# connectors.net
KiCad netlist of a schematic drawn in EAGLE
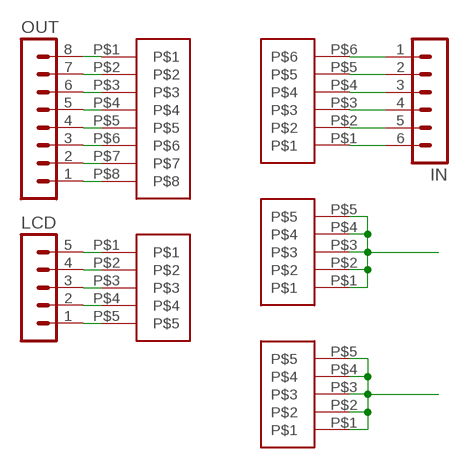
[diagram p0: schematic, sheet 1]

(export (version "E")
  (design (tool "Eeschema 10.0.6"))
  (components
    (comp (ref "IN")
      (value "MA06-1")
      (footprint "eagle-import:MA06-1")
      (libsource (lib "eagle-import") (part "MA06-1"))
    )
    (comp (ref "LCD")
      (value "MA05-1")
      (footprint "eagle-import:MA05-1")
      (libsource (lib "eagle-import") (part "MA05-1"))
    )
    (comp (ref "OUT")
      (value "MA08-1")
      (footprint "eagle-import:MA08-1")
      (libsource (lib "eagle-import") (part "MA08-1"))
    )
    (comp (ref "U$1")
      (value "KOSTKA_2.5MM_X8")
      (footprint "eagle-import:X8")
      (libsource (lib "eagle-import") (part "KOSTKA_2.5MM_X8"))
    )
    (comp (ref "U$2")
      (value "KOSTKA_2.5MM_X5")
      (footprint "eagle-import:X5")
      (libsource (lib "eagle-import") (part "KOSTKA_2.5MM_X5"))
    )
    (comp (ref "U$3")
      (value "KOSTKA_2.5MM_X6")
      (footprint "eagle-import:X6")
      (libsource (lib "eagle-import") (part "KOSTKA_2.5MM_X6"))
    )
    (comp (ref "U$4")
      (value "KOSTKA_2.5MM_X5")
      (footprint "eagle-import:X5")
      (libsource (lib "eagle-import") (part "KOSTKA_2.5MM_X5"))
    )
    (comp (ref "U$6")
      (value "KOSTKA_2.5MM_X5")
      (footprint "eagle-import:X5")
      (libsource (lib "eagle-import") (part "KOSTKA_2.5MM_X5"))
    )
  )
  (nets
    (net (code "1") (name "Net-(IN-Pad1)") (class "Default")
      (node (ref "IN") (pin "1") (pinfunction "1_1") (pintype "passive"))
      (node (ref "U$3") (pin "P$6") (pinfunction "P$6_P$6") (pintype "bidirectional"))
    )
    (net (code "2") (name "Net-(IN-Pad2)") (class "Default")
      (node (ref "IN") (pin "2") (pinfunction "2_2") (pintype "passive"))
      (node (ref "U$3") (pin "P$5") (pinfunction "P$5_P$5") (pintype "bidirectional"))
    )
    (net (code "3") (name "Net-(IN-Pad3)") (class "Default")
      (node (ref "IN") (pin "3") (pinfunction "3_3") (pintype "passive"))
      (node (ref "U$3") (pin "P$4") (pinfunction "P$4_P$4") (pintype "bidirectional"))
    )
    (net (code "4") (name "Net-(IN-Pad4)") (class "Default")
      (node (ref "IN") (pin "4") (pinfunction "4_4") (pintype "passive"))
      (node (ref "U$3") (pin "P$3") (pinfunction "P$3_P$3") (pintype "bidirectional"))
    )
    (net (code "5") (name "Net-(IN-Pad5)") (class "Default")
      (node (ref "IN") (pin "5") (pinfunction "5_5") (pintype "passive"))
      (node (ref "U$3") (pin "P$2") (pinfunction "P$2_P$2") (pintype "bidirectional"))
    )
    (net (code "6") (name "Net-(IN-Pad6)") (class "Default")
      (node (ref "IN") (pin "6") (pinfunction "6_6") (pintype "passive"))
      (node (ref "U$3") (pin "P$1") (pinfunction "P$1_P$1") (pintype "bidirectional"))
    )
    (net (code "7") (name "Net-(LCD-Pad1)") (class "Default")
      (node (ref "LCD") (pin "1") (pinfunction "1_1") (pintype "passive"))
      (node (ref "U$6") (pin "P$5") (pinfunction "P$5_P$5") (pintype "bidirectional"))
    )
    (net (code "8") (name "Net-(LCD-Pad2)") (class "Default")
      (node (ref "LCD") (pin "2") (pinfunction "2_2") (pintype "passive"))
      (node (ref "U$6") (pin "P$4") (pinfunction "P$4_P$4") (pintype "bidirectional"))
    )
    (net (code "9") (name "Net-(LCD-Pad3)") (class "Default")
      (node (ref "LCD") (pin "3") (pinfunction "3_3") (pintype "passive"))
      (node (ref "U$6") (pin "P$3") (pinfunction "P$3_P$3") (pintype "bidirectional"))
    )
    (net (code "10") (name "Net-(LCD-Pad4)") (class "Default")
      (node (ref "LCD") (pin "4") (pinfunction "4_4") (pintype "passive"))
      (node (ref "U$6") (pin "P$2") (pinfunction "P$2_P$2") (pintype "bidirectional"))
    )
    (net (code "11") (name "Net-(LCD-Pad5)") (class "Default")
      (node (ref "LCD") (pin "5") (pinfunction "5_5") (pintype "passive"))
      (node (ref "U$6") (pin "P$1") (pinfunction "P$1_P$1") (pintype "bidirectional"))
    )
    (net (code "12") (name "Net-(OUT-Pad1)") (class "Default")
      (node (ref "OUT") (pin "1") (pinfunction "1_1") (pintype "passive"))
      (node (ref "U$1") (pin "P$8") (pinfunction "P$8_P$8") (pintype "bidirectional"))
    )
    (net (code "13") (name "Net-(OUT-Pad2)") (class "Default")
      (node (ref "OUT") (pin "2") (pinfunction "2_2") (pintype "passive"))
      (node (ref "U$1") (pin "P$7") (pinfunction "P$7_P$7") (pintype "bidirectional"))
    )
    (net (code "14") (name "Net-(OUT-Pad3)") (class "Default")
      (node (ref "OUT") (pin "3") (pinfunction "3_3") (pintype "passive"))
      (node (ref "U$1") (pin "P$6") (pinfunction "P$6_P$6") (pintype "bidirectional"))
    )
    (net (code "15") (name "Net-(OUT-Pad4)") (class "Default")
      (node (ref "OUT") (pin "4") (pinfunction "4_4") (pintype "passive"))
      (node (ref "U$1") (pin "P$5") (pinfunction "P$5_P$5") (pintype "bidirectional"))
    )
    (net (code "16") (name "Net-(OUT-Pad5)") (class "Default")
      (node (ref "OUT") (pin "5") (pinfunction "5_5") (pintype "passive"))
      (node (ref "U$1") (pin "P$4") (pinfunction "P$4_P$4") (pintype "bidirectional"))
    )
    (net (code "17") (name "Net-(OUT-Pad6)") (class "Default")
      (node (ref "OUT") (pin "6") (pinfunction "6_6") (pintype "passive"))
      (node (ref "U$1") (pin "P$3") (pinfunction "P$3_P$3") (pintype "bidirectional"))
    )
    (net (code "18") (name "Net-(OUT-Pad7)") (class "Default")
      (node (ref "OUT") (pin "7") (pinfunction "7_7") (pintype "passive"))
      (node (ref "U$1") (pin "P$2") (pinfunction "P$2_P$2") (pintype "bidirectional"))
    )
    (net (code "19") (name "Net-(OUT-Pad8)") (class "Default")
      (node (ref "OUT") (pin "8") (pinfunction "8_8") (pintype "passive"))
      (node (ref "U$1") (pin "P$1") (pinfunction "P$1_P$1") (pintype "bidirectional"))
    )
    (net (code "20") (name "Net-(U$2-PadP$1)") (class "Default")
      (node (ref "U$2") (pin "P$1") (pinfunction "P$1_P$1") (pintype "bidirectional"))
      (node (ref "U$2") (pin "P$2") (pinfunction "P$2_P$2") (pintype "bidirectional"))
      (node (ref "U$2") (pin "P$3") (pinfunction "P$3_P$3") (pintype "bidirectional"))
      (node (ref "U$2") (pin "P$4") (pinfunction "P$4_P$4") (pintype "bidirectional"))
      (node (ref "U$2") (pin "P$5") (pinfunction "P$5_P$5") (pintype "bidirectional"))
    )
    (net (code "21") (name "Net-(U$4-PadP$1)") (class "Default")
      (node (ref "U$4") (pin "P$1") (pinfunction "P$1_P$1") (pintype "bidirectional"))
      (node (ref "U$4") (pin "P$2") (pinfunction "P$2_P$2") (pintype "bidirectional"))
      (node (ref "U$4") (pin "P$3") (pinfunction "P$3_P$3") (pintype "bidirectional"))
      (node (ref "U$4") (pin "P$4") (pinfunction "P$4_P$4") (pintype "bidirectional"))
      (node (ref "U$4") (pin "P$5") (pinfunction "P$5_P$5") (pintype "bidirectional"))
    )
  )
)
